# PAGE3.net
KiCad netlist of a schematic drawn in Altium Designer
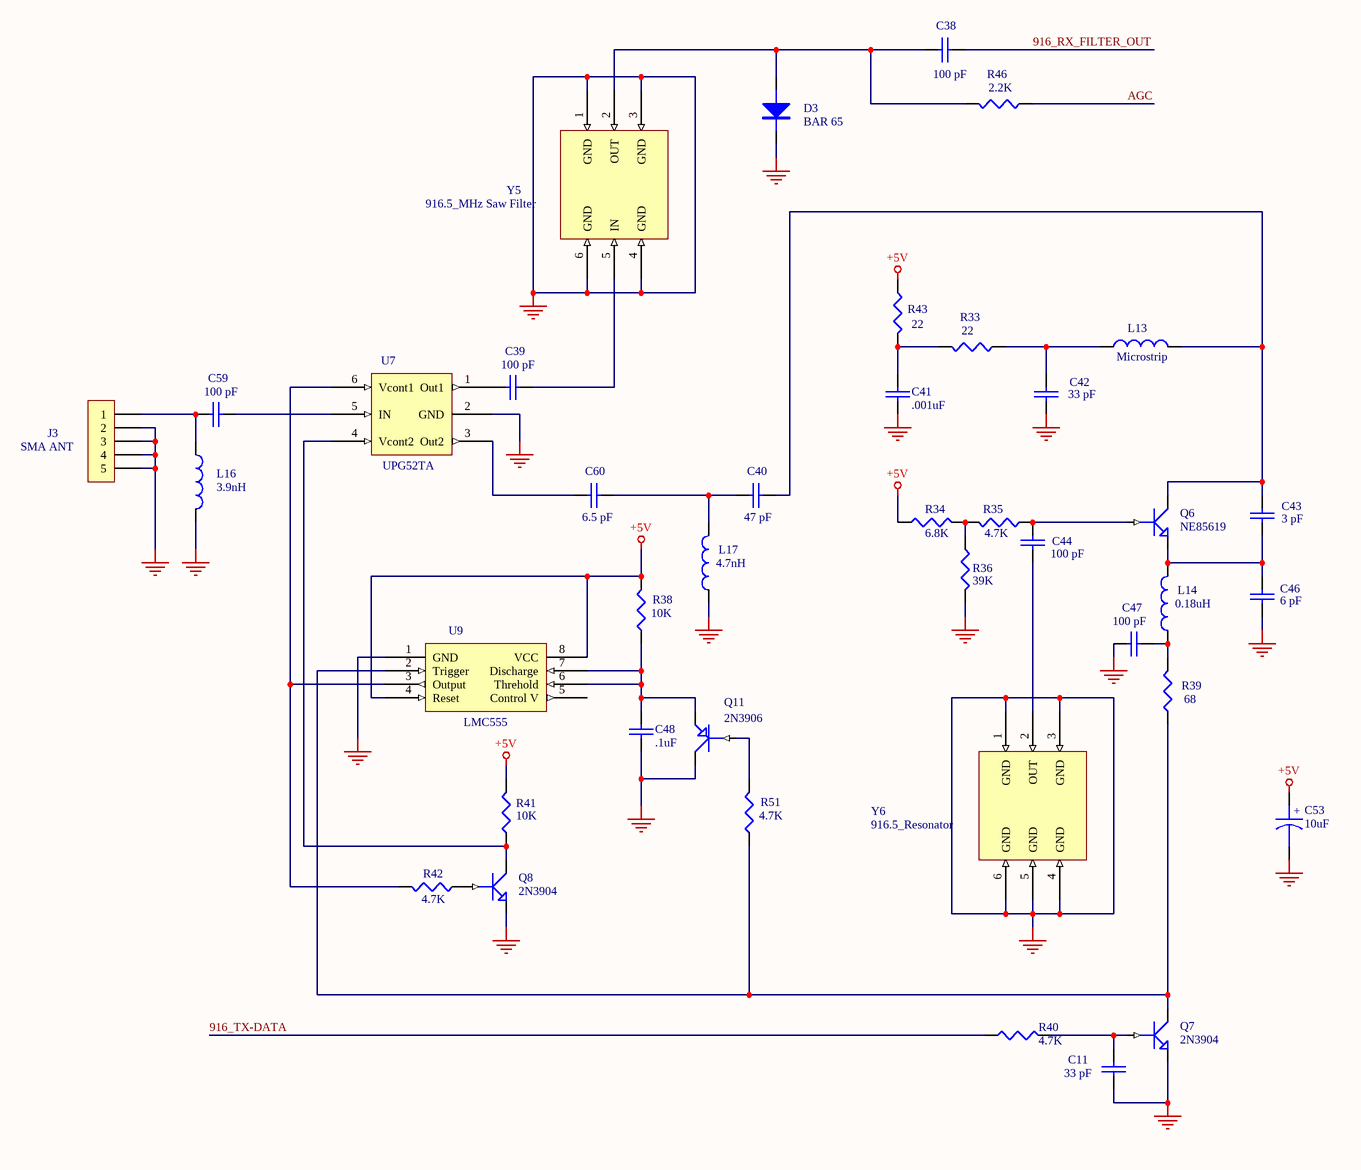
[diagram p0: PAGE3.SCHDOC]

(export (version "E")
  (design (tool "Eeschema 10.0.6"))
  (components
    (comp (ref "C11")
      (value "33 pF")
      (footprint "0603")
      (description "Capacitor")
      (libsource (lib "*") (part "CAP"))
    )
    (comp (ref "C38")
      (value "100 pF")
      (footprint "0603")
      (description "Capacitor")
      (libsource (lib "*") (part "CAP"))
    )
    (comp (ref "C39")
      (value "100 pF")
      (footprint "0603")
      (description "Capacitor")
      (libsource (lib "*") (part "CAP"))
    )
    (comp (ref "C40")
      (value "47 pF")
      (footprint "0603")
      (description "Capacitor")
      (libsource (lib "*") (part "CAP"))
    )
    (comp (ref "C41")
      (value ".001uF")
      (footprint "0603")
      (description "Capacitor")
      (libsource (lib "*") (part "CAP"))
    )
    (comp (ref "C42")
      (value "33 pF")
      (footprint "0603")
      (description "Capacitor")
      (libsource (lib "*") (part "CAP"))
    )
    (comp (ref "C43")
      (value "3 pF")
      (footprint "0603")
      (description "Capacitor")
      (libsource (lib "*") (part "CAP"))
    )
    (comp (ref "C44")
      (value "100 pF")
      (footprint "0603")
      (description "Capacitor")
      (libsource (lib "*") (part "CAP"))
    )
    (comp (ref "C46")
      (value "6 pF")
      (footprint "0603")
      (description "Capacitor")
      (libsource (lib "*") (part "CAP"))
    )
    (comp (ref "C47")
      (value "100 pF")
      (footprint "0603")
      (description "Capacitor")
      (libsource (lib "*") (part "CAP"))
    )
    (comp (ref "C48")
      (value ".1uF")
      (footprint "0603")
      (description "Capacitor")
      (libsource (lib "*") (part "CAP"))
    )
    (comp (ref "C53")
      (value "10uF")
      (footprint "CAP A CASE")
      (description "Capacitor")
      (libsource (lib "*") (part "CAPACITOR POL"))
    )
    (comp (ref "C59")
      (value "100 pF")
      (footprint "0603")
      (description "Capacitor")
      (libsource (lib "*") (part "CAP"))
    )
    (comp (ref "C60")
      (value "6.5 pF")
      (footprint "0603")
      (description "Capacitor")
      (libsource (lib "*") (part "CAP"))
    )
    (comp (ref "D3")
      (value "BAR 65")
      (footprint "DIODE SC79")
      (description "Diode")
      (libsource (lib "*") (part "DIODE"))
    )
    (comp (ref "J3")
      (value "SMA ANT")
      (footprint "50 OHM ANT")
      (description "Connector")
      (libsource (lib "*") (part "CON5"))
    )
    (comp (ref "L13") (value "Microstrip") (footprint "MICROSTRIP") (libsource (lib "*") (part "INDUCTOR")))
    (comp (ref "L14") (value "0.18uH") (footprint "0603") (libsource (lib "*") (part "INDUCTOR")))
    (comp (ref "L16") (value "3.9nH") (footprint "0603") (libsource (lib "*") (part "INDUCTOR")))
    (comp (ref "L17") (value "4.7nH") (footprint "0603") (libsource (lib "*") (part "INDUCTOR")))
    (comp (ref "Q6")
      (value "NE85619")
      (footprint "3 PIN ULTRA SUPER MINI MOLD")
      (description "NPN Transistor")
      (libsource (lib "*") (part "NPN1"))
    )
    (comp (ref "Q7")
      (value "2N3904")
      (footprint "SOT23 TRANS")
      (description "NPN Transistor")
      (libsource (lib "*") (part "NPN1"))
    )
    (comp (ref "Q8")
      (value "2N3904")
      (footprint "SOT23 TRANS")
      (description "NPN Transistor")
      (libsource (lib "*") (part "NPN1"))
    )
    (comp (ref "Q11")
      (value "2N3906")
      (footprint "SOT23 TRANS")
      (description "PNP Transistor")
      (libsource (lib "*") (part "PNP1"))
    )
    (comp (ref "R33") (value "22") (footprint "0603") (libsource (lib "*") (part "RESISTOR")))
    (comp (ref "R34") (value "6.8K") (footprint "0603") (libsource (lib "*") (part "RESISTOR")))
    (comp (ref "R35") (value "4.7K") (footprint "0603") (libsource (lib "*") (part "RESISTOR")))
    (comp (ref "R36") (value "39K") (footprint "0603") (libsource (lib "*") (part "RESISTOR")))
    (comp (ref "R38") (value "10K") (footprint "0603") (libsource (lib "*") (part "RESISTOR")))
    (comp (ref "R39") (value "68") (footprint "0603") (libsource (lib "*") (part "RESISTOR")))
    (comp (ref "R40") (value "4.7K") (footprint "0603") (libsource (lib "*") (part "RESISTOR")))
    (comp (ref "R41") (value "10K") (footprint "0603") (libsource (lib "*") (part "RESISTOR")))
    (comp (ref "R42") (value "4.7K") (footprint "0603") (libsource (lib "*") (part "RESISTOR")))
    (comp (ref "R43") (value "22") (footprint "0603") (libsource (lib "*") (part "RESISTOR")))
    (comp (ref "R46") (value "2.2K") (footprint "0603") (libsource (lib "*") (part "RESISTOR")))
    (comp (ref "R51") (value "4.7K") (footprint "0603") (libsource (lib "*") (part "RESISTOR")))
    (comp (ref "U7") (value "UPG52TA") (footprint "TO6") (libsource (lib "*") (part "UPG152TA_0")))
    (comp (ref "U9") (value "LMC555") (footprint "SO8 SMALL") (libsource (lib "*") (part "LMC555")))
    (comp (ref "Y5") (value "916.5_MHz Saw Filter") (libsource (lib "*") (part "RESONATOR3")))
    (comp (ref "Y6")
      (value "916.5_Resonator")
      (footprint "RESONATOR2")
      (libsource (lib "*") (part "RESONATOR2"))
    )
  )
  (nets
    (net (code "1") (name "+5V") (class "Default")
      (node (ref "C53") (pin "1") (pinfunction "1_1") (pintype "passive"))
      (node (ref "R34") (pin "1") (pinfunction "1_1") (pintype "passive"))
      (node (ref "R38") (pin "2") (pinfunction "2_2") (pintype "passive"))
      (node (ref "R41") (pin "2") (pinfunction "2_2") (pintype "passive"))
      (node (ref "R43") (pin "1") (pinfunction "1_1") (pintype "passive"))
      (node (ref "U9") (pin "4") (pinfunction "Reset_4") (pintype "input"))
      (node (ref "U9") (pin "8") (pinfunction "VCC_8") (pintype "power_in"))
    )
    (net (code "2") (name "/916_RX_FILTER_OUT") (class "Default")
      (node (ref "C38") (pin "2") (pinfunction "2_2") (pintype "passive"))
    )
    (net (code "3") (name "/916_TX-DATA") (class "Default")
      (node (ref "R40") (pin "1") (pinfunction "1_1") (pintype "passive"))
    )
    (net (code "4") (name "/AGC") (class "Default")
      (node (ref "R46") (pin "1") (pinfunction "1_1") (pintype "passive"))
    )
    (net (code "5") (name "GND_SIGNAL") (class "Default")
      (node (ref "C11") (pin "2") (pinfunction "2_2") (pintype "passive"))
      (node (ref "C41") (pin "2") (pinfunction "2_2") (pintype "passive"))
      (node (ref "C42") (pin "2") (pinfunction "2_2") (pintype "passive"))
      (node (ref "C46") (pin "2") (pinfunction "2_2") (pintype "passive"))
      (node (ref "C47") (pin "1") (pinfunction "1_1") (pintype "passive"))
      (node (ref "C48") (pin "2") (pinfunction "2_2") (pintype "passive"))
      (node (ref "C53") (pin "2") (pinfunction "2_2") (pintype "passive"))
      (node (ref "D3") (pin "K") (pinfunction "K_K") (pintype "passive"))
      (node (ref "J3") (pin "2") (pinfunction "2_2") (pintype "passive"))
      (node (ref "J3") (pin "3") (pinfunction "3_3") (pintype "passive"))
      (node (ref "J3") (pin "4") (pinfunction "4_4") (pintype "passive"))
      (node (ref "J3") (pin "5") (pinfunction "5_5") (pintype "passive"))
      (node (ref "L16") (pin "2") (pinfunction "2_2") (pintype "passive"))
      (node (ref "L17") (pin "1") (pinfunction "1_1") (pintype "passive"))
      (node (ref "Q11") (pin "C") (pinfunction "C_C") (pintype "passive"))
      (node (ref "Q7") (pin "E") (pinfunction "E_E") (pintype "passive"))
      (node (ref "Q8") (pin "E") (pinfunction "E_E") (pintype "passive"))
      (node (ref "R36") (pin "2") (pinfunction "2_2") (pintype "passive"))
      (node (ref "U7") (pin "2") (pinfunction "GND_2") (pintype "power_in"))
      (node (ref "U9") (pin "1") (pinfunction "GND_1") (pintype "power_in"))
      (node (ref "Y5") (pin "1") (pinfunction "GND_1") (pintype "input"))
      (node (ref "Y5") (pin "3") (pinfunction "GND_3") (pintype "input"))
      (node (ref "Y5") (pin "4") (pinfunction "GND_4") (pintype "input"))
      (node (ref "Y5") (pin "6") (pinfunction "GND_6") (pintype "input"))
      (node (ref "Y6") (pin "1") (pinfunction "GND_1") (pintype "input"))
      (node (ref "Y6") (pin "3") (pinfunction "GND_3") (pintype "input"))
      (node (ref "Y6") (pin "4") (pinfunction "GND_4") (pintype "input"))
      (node (ref "Y6") (pin "5") (pinfunction "GND_5") (pintype "input"))
      (node (ref "Y6") (pin "6") (pinfunction "GND_6") (pintype "input"))
    )
    (net (code "6") (name "Net-(C11-Pad1)") (class "Default")
      (node (ref "C11") (pin "1") (pinfunction "1_1") (pintype "passive"))
      (node (ref "Q7") (pin "B") (pinfunction "B_B") (pintype "input"))
      (node (ref "R40") (pin "2") (pinfunction "2_2") (pintype "passive"))
    )
    (net (code "7") (name "Net-(C40-Pad1)") (class "Default")
      (node (ref "C40") (pin "1") (pinfunction "1_1") (pintype "passive"))
      (node (ref "C60") (pin "2") (pinfunction "2_2") (pintype "passive"))
      (node (ref "L17") (pin "2") (pinfunction "2_2") (pintype "passive"))
    )
    (net (code "8") (name "Net-(C40-Pad2)") (class "Default")
      (node (ref "C40") (pin "2") (pinfunction "2_2") (pintype "passive"))
      (node (ref "C43") (pin "1") (pinfunction "1_1") (pintype "passive"))
      (node (ref "L13") (pin "2") (pinfunction "2_2") (pintype "passive"))
      (node (ref "Q6") (pin "C") (pinfunction "C_C") (pintype "passive"))
    )
    (net (code "9") (name "Net-(C41-Pad1)") (class "Default")
      (node (ref "C41") (pin "1") (pinfunction "1_1") (pintype "passive"))
      (node (ref "R33") (pin "2") (pinfunction "2_2") (pintype "passive"))
      (node (ref "R43") (pin "2") (pinfunction "2_2") (pintype "passive"))
    )
    (net (code "10") (name "Net-(C42-Pad1)") (class "Default")
      (node (ref "C42") (pin "1") (pinfunction "1_1") (pintype "passive"))
      (node (ref "L13") (pin "1") (pinfunction "1_1") (pintype "passive"))
      (node (ref "R33") (pin "1") (pinfunction "1_1") (pintype "passive"))
    )
    (net (code "11") (name "Net-(C43-Pad2)") (class "Default")
      (node (ref "C43") (pin "2") (pinfunction "2_2") (pintype "passive"))
      (node (ref "C46") (pin "1") (pinfunction "1_1") (pintype "passive"))
      (node (ref "L14") (pin "2") (pinfunction "2_2") (pintype "passive"))
      (node (ref "Q6") (pin "E") (pinfunction "E_E") (pintype "passive"))
    )
    (net (code "12") (name "Net-(C44-Pad1)") (class "Default")
      (node (ref "C44") (pin "1") (pinfunction "1_1") (pintype "passive"))
      (node (ref "Q6") (pin "B") (pinfunction "B_B") (pintype "input"))
      (node (ref "R35") (pin "1") (pinfunction "1_1") (pintype "passive"))
    )
    (net (code "13") (name "Net-(C47-Pad2)") (class "Default")
      (node (ref "C47") (pin "2") (pinfunction "2_2") (pintype "passive"))
      (node (ref "L14") (pin "1") (pinfunction "1_1") (pintype "passive"))
      (node (ref "R39") (pin "2") (pinfunction "2_2") (pintype "passive"))
    )
    (net (code "14") (name "Net-(C59-Pad1)") (class "Default")
      (node (ref "C59") (pin "1") (pinfunction "1_1") (pintype "passive"))
      (node (ref "J3") (pin "1") (pinfunction "1_1") (pintype "passive"))
      (node (ref "L16") (pin "1") (pinfunction "1_1") (pintype "passive"))
    )
    (net (code "15") (name "Net-(Q8-PadB)") (class "Default")
      (node (ref "Q8") (pin "B") (pinfunction "B_B") (pintype "input"))
      (node (ref "R42") (pin "1") (pinfunction "1_1") (pintype "passive"))
    )
    (net (code "16") (name "Net-(Q11-PadB)") (class "Default")
      (node (ref "Q11") (pin "B") (pinfunction "B_B") (pintype "input"))
      (node (ref "R51") (pin "2") (pinfunction "2_2") (pintype "passive"))
    )
    (net (code "17") (name "Net-(R34-Pad2)") (class "Default")
      (node (ref "R34") (pin "2") (pinfunction "2_2") (pintype "passive"))
      (node (ref "R35") (pin "2") (pinfunction "2_2") (pintype "passive"))
      (node (ref "R36") (pin "1") (pinfunction "1_1") (pintype "passive"))
    )
    (net (code "18") (name "Net-(U7-IN)") (class "Default")
      (node (ref "C59") (pin "2") (pinfunction "2_2") (pintype "passive"))
      (node (ref "U7") (pin "5") (pinfunction "IN_5") (pintype "input"))
    )
    (net (code "19") (name "Net-(U7-Out1)") (class "Default")
      (node (ref "C39") (pin "1") (pinfunction "1_1") (pintype "passive"))
      (node (ref "U7") (pin "1") (pinfunction "Out1_1") (pintype "output"))
    )
    (net (code "20") (name "Net-(U7-Out2)") (class "Default")
      (node (ref "C60") (pin "1") (pinfunction "1_1") (pintype "passive"))
      (node (ref "U7") (pin "3") (pinfunction "Out2_3") (pintype "output"))
    )
    (net (code "21") (name "Net-(U7-Vcont1)") (class "Default")
      (node (ref "R42") (pin "2") (pinfunction "2_2") (pintype "passive"))
      (node (ref "U7") (pin "6") (pinfunction "Vcont1_6") (pintype "input"))
      (node (ref "U9") (pin "3") (pinfunction "Output_3") (pintype "output"))
    )
    (net (code "22") (name "Net-(U7-Vcont2)") (class "Default")
      (node (ref "Q8") (pin "C") (pinfunction "C_C") (pintype "passive"))
      (node (ref "R41") (pin "1") (pinfunction "1_1") (pintype "passive"))
      (node (ref "U7") (pin "4") (pinfunction "Vcont2_4") (pintype "input"))
    )
    (net (code "23") (name "Net-(U9-Discharge)") (class "Default")
      (node (ref "C48") (pin "1") (pinfunction "1_1") (pintype "passive"))
      (node (ref "Q11") (pin "E") (pinfunction "E_E") (pintype "passive"))
      (node (ref "R38") (pin "1") (pinfunction "1_1") (pintype "passive"))
      (node (ref "U9") (pin "6") (pinfunction "Threhold_6") (pintype "input"))
      (node (ref "U9") (pin "7") (pinfunction "Discharge_7") (pintype "input"))
    )
    (net (code "24") (name "Net-(U9-Trigger)") (class "Default")
      (node (ref "Q7") (pin "C") (pinfunction "C_C") (pintype "passive"))
      (node (ref "R39") (pin "1") (pinfunction "1_1") (pintype "passive"))
      (node (ref "R51") (pin "1") (pinfunction "1_1") (pintype "passive"))
      (node (ref "U9") (pin "2") (pinfunction "Trigger_2") (pintype "input"))
    )
    (net (code "25") (name "Net-(Y5-IN)") (class "Default")
      (node (ref "C39") (pin "2") (pinfunction "2_2") (pintype "passive"))
      (node (ref "Y5") (pin "5") (pinfunction "IN_5") (pintype "input"))
    )
    (net (code "26") (name "Net-(Y5-OUT)") (class "Default")
      (node (ref "C38") (pin "1") (pinfunction "1_1") (pintype "passive"))
      (node (ref "D3") (pin "A") (pinfunction "A_A") (pintype "passive"))
      (node (ref "R46") (pin "2") (pinfunction "2_2") (pintype "passive"))
      (node (ref "Y5") (pin "2") (pinfunction "OUT_2") (pintype "input"))
    )
    (net (code "27") (name "Net-(Y6-OUT)") (class "Default")
      (node (ref "C44") (pin "2") (pinfunction "2_2") (pintype "passive"))
      (node (ref "Y6") (pin "2") (pinfunction "OUT_2") (pintype "input"))
    )
    (net (code "28") (name "unconnected-(U9-Control_V-Pad5)") (class "Default")
      (node (ref "U9") (pin "5") (pinfunction "Control_V_5") (pintype "output"))
    )
  )
)
